# DVL_Interface.net
KiCad netlist of a schematic drawn in Altium Designer
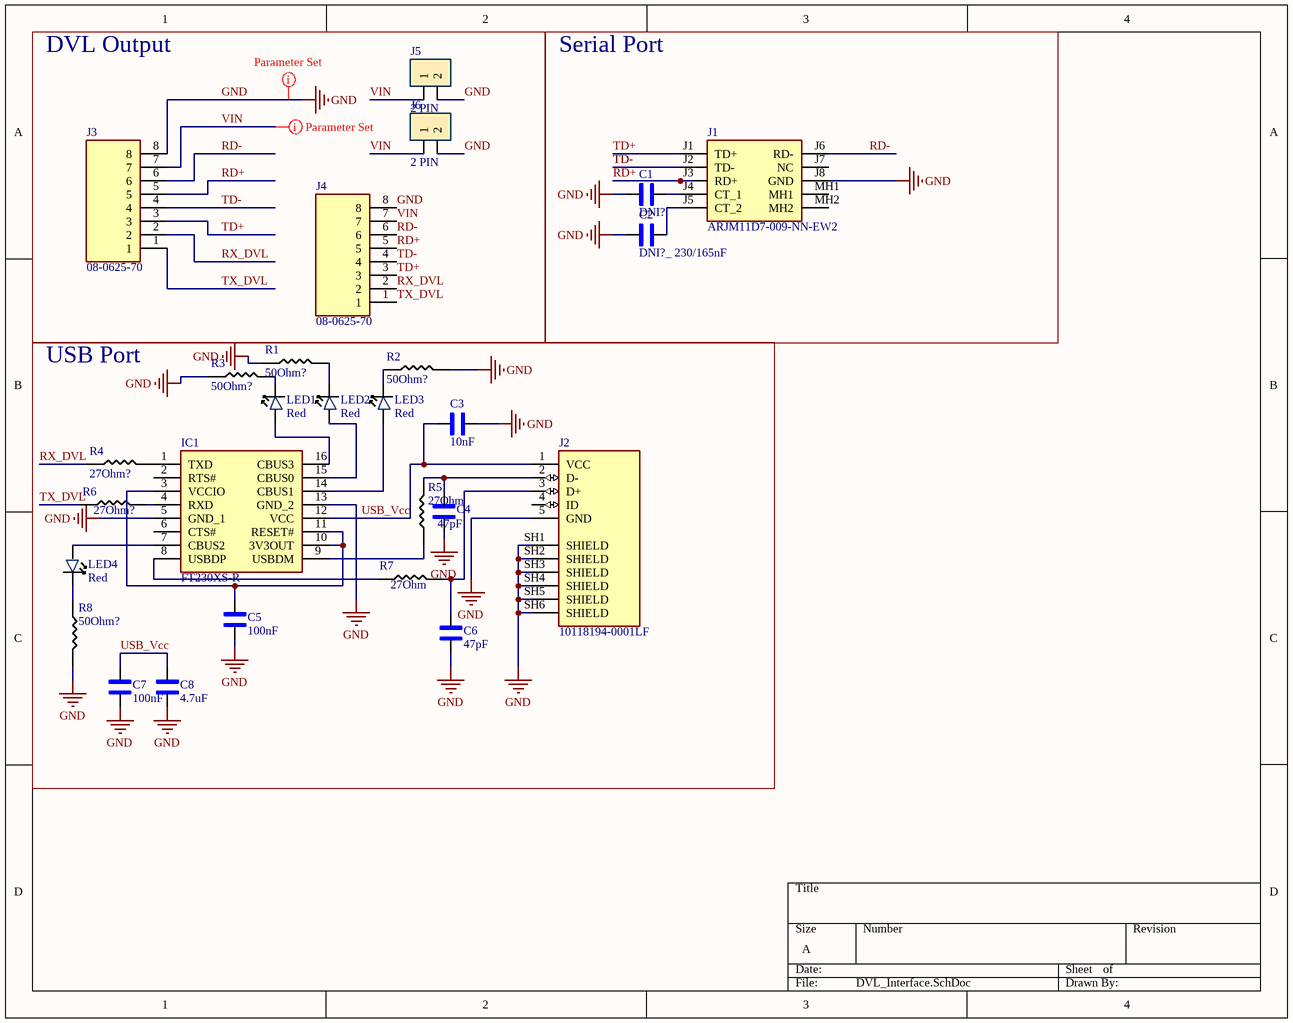
[diagram p0: DVL_Interface.SchDoc]

(export (version "E")
  (design (tool "Eeschema 10.0.6"))
  (components
    (comp (ref "C1")
      (value "DNI?")
      (footprint "1206_Passive_Capacitor")
      (description "10uF ±10% 50V X5R 1206 Multilayer Ceramic Capacitors MLCC - SMD/SMT RoHS")
      (fields (field (name "LCSC PART#") "C13585") (field (name "MFR PART #") "CL31A106KBHNNNE"))
      (libsource (lib "ECEN5730Lib_2023_05_DS") (part "C_10uF_1206"))
    )
    (comp (ref "C2")
      (value "DNI?_ 230/165nF")
      (footprint "1206_Passive_Capacitor")
      (description "10uF ±10% 50V X5R 1206 Multilayer Ceramic Capacitors MLCC - SMD/SMT RoHS")
      (fields (field (name "LCSC PART#") "C13585") (field (name "MFR PART #") "CL31A106KBHNNNE"))
      (libsource (lib "ECEN5730Lib_2023_05_DS") (part "C_10uF_1206"))
    )
    (comp (ref "C3")
      (value "10nF")
      (footprint "1206_Passive_Capacitor")
      (description "10uF ±10% 50V X5R 1206 Multilayer Ceramic Capacitors MLCC - SMD/SMT RoHS")
      (fields (field (name "LCSC PART#") "C13585") (field (name "MFR PART #") "CL31A106KBHNNNE"))
      (libsource (lib "ECEN5730Lib_2023_05_DS") (part "C_10uF_1206"))
    )
    (comp (ref "C4")
      (value "47pF")
      (footprint "1206_Passive_Capacitor")
      (description "47nF ±5% 50V C0G 1206 Multilayer Ceramic Capacitors MLCC - SMD/SMT RoHS")
      (fields (field (name "LCSC PART#") "C21812") (field (name "MFR PART #") "GRM31M5C1H473JA01L"))
      (libsource (lib "ECEN5730Lib_2023_05_DS") (part "C_47nF_1206"))
    )
    (comp (ref "C5")
      (value "100nF")
      (footprint "1206_Passive_Capacitor")
      (description "10uF ±10% 50V X5R 1206 Multilayer Ceramic Capacitors MLCC - SMD/SMT RoHS")
      (fields (field (name "LCSC PART#") "C13585") (field (name "MFR PART #") "CL31A106KBHNNNE"))
      (libsource (lib "ECEN5730Lib_2023_05_DS") (part "C_10uF_1206"))
    )
    (comp (ref "C6")
      (value "47pF")
      (footprint "1206_Passive_Capacitor")
      (description "47nF ±5% 50V C0G 1206 Multilayer Ceramic Capacitors MLCC - SMD/SMT RoHS")
      (fields (field (name "LCSC PART#") "C21812") (field (name "MFR PART #") "GRM31M5C1H473JA01L"))
      (libsource (lib "ECEN5730Lib_2023_05_DS") (part "C_47nF_1206"))
    )
    (comp (ref "C7")
      (value "100nF")
      (footprint "1206_Passive_Capacitor")
      (description "10uF ±10% 50V X5R 1206 Multilayer Ceramic Capacitors MLCC - SMD/SMT RoHS")
      (fields (field (name "LCSC PART#") "C13585") (field (name "MFR PART #") "CL31A106KBHNNNE"))
      (libsource (lib "ECEN5730Lib_2023_05_DS") (part "C_10uF_1206"))
    )
    (comp (ref "C8")
      (value "4.7uF")
      (footprint "1206_Passive_Capacitor")
      (description "10uF ±10% 50V X5R 1206 Multilayer Ceramic Capacitors MLCC - SMD/SMT RoHS")
      (fields (field (name "LCSC PART#") "C13585") (field (name "MFR PART #") "CL31A106KBHNNNE"))
      (libsource (lib "ECEN5730Lib_2023_05_DS") (part "C_10uF_1206"))
    )
    (comp (ref "IC1")
      (value "FT230XS-R")
      (footprint "SamacSys:SOP64P599X175-16N")
      (description "Integrated Circuit")
      (fields (field (name "MOUSER PART NUMBER") "895-FT230XS-R"))
      (libsource (lib "*") (part "FT230XS-R"))
    )
    (comp (ref "J1")
      (value "ARJM11D7-009-NN-EW2")
      (footprint "SamacSys:ARJM11D7009NNEW2")
      (description "Connector")
      (fields (field (name "MOUSER PART NUMBER") "815-RJM11D7009NNEW2"))
      (libsource (lib "*") (part "ARJM11D7-009-NN-EW2"))
    )
    (comp (ref "J2")
      (value "10118194-0001LF")
      (footprint "AMPHENOL_10118194-0001LF")
      (description "Micro USB, Input Output Connectors, B TYPE RECEPTACLE with flange")
      (fields (field (name "MF") "Amphenol ICC"))
      (libsource (lib "10118194-0001LF") (part "10118194-0001LF"))
    )
    (comp (ref "J3")
      (value "08-0625-70")
      (footprint "SamacSys:HDRV8W51P0X254_1X8_2032X254X816P")
      (description "Connector")
      (fields (field (name "MOUSER PART NUMBER") "535-08-0625-70"))
      (libsource (lib "*") (part "08-0625-70"))
    )
    (comp (ref "J4")
      (value "08-0625-70")
      (footprint "SamacSys:HDRV8W51P0X254_1X8_2032X254X816P")
      (description "Connector")
      (fields (field (name "MOUSER PART NUMBER") "535-08-0625-70"))
      (libsource (lib "*") (part "08-0625-70"))
    )
    (comp (ref "J5")
      (value "2 PIN")
      (footprint "2_PIN_100MIL")
      (description "2.54mm Straight 2 1 Header，Breakaway Through Hole,P=2.54mm Pin Header & Female Header ROHS")
      (fields (field (name "LCSC PART#") "C124375") (field (name "MFR PART #") "B-2100S02P-A110"))
      (libsource (lib "ECEN5730Lib_2023_05_DS") (part "JM_2_PIN_MALE"))
    )
    (comp (ref "J6")
      (value "2 PIN")
      (footprint "2_PIN_100MIL")
      (description "2.54mm Straight 2 1 Header，Breakaway Through Hole,P=2.54mm Pin Header & Female Header ROHS")
      (fields (field (name "LCSC PART#") "C124375") (field (name "MFR PART #") "B-2100S02P-A110"))
      (libsource (lib "ECEN5730Lib_2023_05_DS") (part "JM_2_PIN_MALE"))
    )
    (comp (ref "LED1")
      (value "Red")
      (footprint "LED_1206")
      (description "Red 621~631nm 1206 Light Emitting Diodes (LED) RoHS")
      (fields (field (name "MFR PART #") "15-21/R6C-FQ1R1B/2T") (field (name "LCSC PART#") "C93133"))
      (libsource (lib "ECEN5730Lib_2023_05_DS") (part "LED_RED_1206"))
    )
    (comp (ref "LED2")
      (value "Red")
      (footprint "LED_1206")
      (description "Red 621~631nm 1206 Light Emitting Diodes (LED) RoHS")
      (fields (field (name "MFR PART #") "15-21/R6C-FQ1R1B/2T") (field (name "LCSC PART#") "C93133"))
      (libsource (lib "ECEN5730Lib_2023_05_DS") (part "LED_RED_1206"))
    )
    (comp (ref "LED3")
      (value "Red")
      (footprint "LED_1206")
      (description "Red 621~631nm 1206 Light Emitting Diodes (LED) RoHS")
      (fields (field (name "MFR PART #") "15-21/R6C-FQ1R1B/2T") (field (name "LCSC PART#") "C93133"))
      (libsource (lib "ECEN5730Lib_2023_05_DS") (part "LED_RED_1206"))
    )
    (comp (ref "LED4")
      (value "Red")
      (footprint "LED_1206")
      (description "Red 621~631nm 1206 Light Emitting Diodes (LED) RoHS")
      (fields (field (name "MFR PART #") "15-21/R6C-FQ1R1B/2T") (field (name "LCSC PART#") "C93133"))
      (libsource (lib "ECEN5730Lib_2023_05_DS") (part "LED_RED_1206"))
    )
    (comp (ref "R1")
      (value "50Ohm?")
      (footprint "1206_Passive_Resitor")
      (description "10 kOhms ±5% 0.25W, 1/4W Chip Resistor 1206 (3216 Metric) Automotive AEC-Q200 Thick Film")
      (fields (field (name "MFR PART #") "RMCF1206FT10K0") (field (name "LCSC PART#") "C17902"))
      (libsource (lib "ECEN5730Lib_2023_05_DS") (part "R_10KOhm_1206"))
    )
    (comp (ref "R2")
      (value "50Ohm?")
      (footprint "1206_Passive_Resitor")
      (description "10 kOhms ±5% 0.25W, 1/4W Chip Resistor 1206 (3216 Metric) Automotive AEC-Q200 Thick Film")
      (fields (field (name "MFR PART #") "RMCF1206FT10K0") (field (name "LCSC PART#") "C17902"))
      (libsource (lib "ECEN5730Lib_2023_05_DS") (part "R_10KOhm_1206"))
    )
    (comp (ref "R3")
      (value "50Ohm?")
      (footprint "1206_Passive_Resitor")
      (description "10 kOhms ±5% 0.25W, 1/4W Chip Resistor 1206 (3216 Metric) Automotive AEC-Q200 Thick Film")
      (fields (field (name "MFR PART #") "RMCF1206FT10K0") (field (name "LCSC PART#") "C17902"))
      (libsource (lib "ECEN5730Lib_2023_05_DS") (part "R_10KOhm_1206"))
    )
    (comp (ref "R4")
      (value "27Ohm?")
      (footprint "1206_Passive_Resitor")
      (description "10 kOhms ±5% 0.25W, 1/4W Chip Resistor 1206 (3216 Metric) Automotive AEC-Q200 Thick Film")
      (fields (field (name "MFR PART #") "RMCF1206FT10K0") (field (name "LCSC PART#") "C17902"))
      (libsource (lib "ECEN5730Lib_2023_05_DS") (part "R_10KOhm_1206"))
    )
    (comp (ref "R5")
      (value "27Ohm")
      (footprint "1206_Passive_Resitor")
      (description "CHIP RESISTOR - SURFACE MOUNT 22OHMS ±1% 1/4W 1206 ROHS")
      (fields (field (name "MFR PART #") "1206W4F220JT5E") (field (name "LCSC PART#") "C17958"))
      (libsource (lib "ECEN5730Lib_2023_05_DS") (part "R_22Ohm_1206"))
    )
    (comp (ref "R6")
      (value "27Ohm?")
      (footprint "1206_Passive_Resitor")
      (description "10 kOhms ±5% 0.25W, 1/4W Chip Resistor 1206 (3216 Metric) Automotive AEC-Q200 Thick Film")
      (fields (field (name "MFR PART #") "RMCF1206FT10K0") (field (name "LCSC PART#") "C17902"))
      (libsource (lib "ECEN5730Lib_2023_05_DS") (part "R_10KOhm_1206"))
    )
    (comp (ref "R7")
      (value "27Ohm")
      (footprint "1206_Passive_Resitor")
      (description "CHIP RESISTOR - SURFACE MOUNT 22OHMS ±1% 1/4W 1206 ROHS")
      (fields (field (name "MFR PART #") "1206W4F220JT5E") (field (name "LCSC PART#") "C17958"))
      (libsource (lib "ECEN5730Lib_2023_05_DS") (part "R_22Ohm_1206"))
    )
    (comp (ref "R8")
      (value "50Ohm?")
      (footprint "1206_Passive_Resitor")
      (description "10 kOhms ±5% 0.25W, 1/4W Chip Resistor 1206 (3216 Metric) Automotive AEC-Q200 Thick Film")
      (fields (field (name "MFR PART #") "RMCF1206FT10K0") (field (name "LCSC PART#") "C17902"))
      (libsource (lib "ECEN5730Lib_2023_05_DS") (part "R_10KOhm_1206"))
    )
  )
  (nets
    (net (code "1") (name "/RD+") (class "Default")
      (node (ref "J1") (pin "J3") (pinfunction "RD+_J3") (pintype "passive"))
      (node (ref "J3") (pin "5") (pinfunction "5_5") (pintype "passive"))
      (node (ref "J4") (pin "5") (pinfunction "5_5") (pintype "passive"))
    )
    (net (code "2") (name "/RD-") (class "Default")
      (node (ref "J1") (pin "J6") (pinfunction "RD-_J6") (pintype "passive"))
      (node (ref "J3") (pin "6") (pinfunction "6_6") (pintype "passive"))
      (node (ref "J4") (pin "6") (pinfunction "6_6") (pintype "passive"))
    )
    (net (code "3") (name "/RX_DVL") (class "Default")
      (node (ref "J3") (pin "2") (pinfunction "2_2") (pintype "passive"))
      (node (ref "J4") (pin "2") (pinfunction "2_2") (pintype "passive"))
      (node (ref "R4") (pin "1") (pinfunction "1_1") (pintype "passive"))
    )
    (net (code "4") (name "/TD+") (class "Default")
      (node (ref "J1") (pin "J1") (pinfunction "TD+_J1") (pintype "passive"))
      (node (ref "J3") (pin "3") (pinfunction "3_3") (pintype "passive"))
      (node (ref "J4") (pin "3") (pinfunction "3_3") (pintype "passive"))
    )
    (net (code "5") (name "/TD-") (class "Default")
      (node (ref "J1") (pin "J2") (pinfunction "TD-_J2") (pintype "passive"))
      (node (ref "J3") (pin "4") (pinfunction "4_4") (pintype "passive"))
      (node (ref "J4") (pin "4") (pinfunction "4_4") (pintype "passive"))
    )
    (net (code "6") (name "/TX_DVL") (class "Default")
      (node (ref "J3") (pin "1") (pinfunction "1_1") (pintype "passive"))
      (node (ref "J4") (pin "1") (pinfunction "1_1") (pintype "passive"))
      (node (ref "R6") (pin "1") (pinfunction "1_1") (pintype "passive"))
    )
    (net (code "7") (name "/USB_Vcc") (class "Default")
      (node (ref "C3") (pin "2") (pinfunction "2_2") (pintype "passive"))
      (node (ref "C7") (pin "2") (pinfunction "2_2") (pintype "passive"))
      (node (ref "C8") (pin "2") (pinfunction "2_2") (pintype "passive"))
      (node (ref "IC1") (pin "12") (pinfunction "VCC_12") (pintype "passive"))
      (node (ref "J2") (pin "1") (pinfunction "VCC_1") (pintype "power_in"))
    )
    (net (code "8") (name "/VIN") (class "Default")
      (node (ref "J3") (pin "7") (pinfunction "7_7") (pintype "passive"))
      (node (ref "J4") (pin "7") (pinfunction "7_7") (pintype "passive"))
      (node (ref "J5") (pin "1") (pinfunction "1_1") (pintype "passive"))
      (node (ref "J6") (pin "1") (pinfunction "1_1") (pintype "passive"))
    )
    (net (code "9") (name "GND") (class "Default")
      (node (ref "C1") (pin "2") (pinfunction "2_2") (pintype "passive"))
      (node (ref "C2") (pin "2") (pinfunction "2_2") (pintype "passive"))
      (node (ref "C3") (pin "1") (pinfunction "1_1") (pintype "passive"))
      (node (ref "C4") (pin "1") (pinfunction "1_1") (pintype "passive"))
      (node (ref "C5") (pin "1") (pinfunction "1_1") (pintype "passive"))
      (node (ref "C6") (pin "1") (pinfunction "1_1") (pintype "passive"))
      (node (ref "C7") (pin "1") (pinfunction "1_1") (pintype "passive"))
      (node (ref "C8") (pin "1") (pinfunction "1_1") (pintype "passive"))
      (node (ref "IC1") (pin "13") (pinfunction "GND_2_13") (pintype "passive"))
      (node (ref "IC1") (pin "5") (pinfunction "GND_1_5") (pintype "passive"))
      (node (ref "J1") (pin "J8") (pinfunction "GND_J8") (pintype "passive"))
      (node (ref "J2") (pin "5") (pinfunction "GND_5") (pintype "power_in"))
      (node (ref "J2") (pin "SH1") (pinfunction "SHIELD_SH1") (pintype "passive"))
      (node (ref "J2") (pin "SH2") (pinfunction "SHIELD_SH2") (pintype "passive"))
      (node (ref "J2") (pin "SH3") (pinfunction "SHIELD_SH3") (pintype "passive"))
      (node (ref "J2") (pin "SH4") (pinfunction "SHIELD_SH4") (pintype "passive"))
      (node (ref "J2") (pin "SH5") (pinfunction "SHIELD_SH5") (pintype "passive"))
      (node (ref "J2") (pin "SH6") (pinfunction "SHIELD_SH6") (pintype "passive"))
      (node (ref "J3") (pin "8") (pinfunction "8_8") (pintype "passive"))
      (node (ref "J4") (pin "8") (pinfunction "8_8") (pintype "passive"))
      (node (ref "J5") (pin "2") (pinfunction "2_2") (pintype "passive"))
      (node (ref "J6") (pin "2") (pinfunction "2_2") (pintype "passive"))
      (node (ref "R1") (pin "1") (pinfunction "1_1") (pintype "passive"))
      (node (ref "R2") (pin "2") (pinfunction "2_2") (pintype "passive"))
      (node (ref "R3") (pin "1") (pinfunction "1_1") (pintype "passive"))
      (node (ref "R8") (pin "2") (pinfunction "2_2") (pintype "passive"))
    )
    (net (code "10") (name "Net-(IC1-3V3OUT)") (class "Default")
      (node (ref "C5") (pin "2") (pinfunction "2_2") (pintype "passive"))
      (node (ref "IC1") (pin "10") (pinfunction "3V3OUT_10") (pintype "passive"))
      (node (ref "IC1") (pin "11") (pinfunction "RESET#_11") (pintype "passive"))
      (node (ref "IC1") (pin "3") (pinfunction "VCCIO_3") (pintype "passive"))
    )
    (net (code "11") (name "Net-(IC1-CBUS0)") (class "Default")
      (node (ref "IC1") (pin "15") (pinfunction "CBUS0_15") (pintype "passive"))
      (node (ref "LED2") (pin "1") (pinfunction "1_1") (pintype "passive"))
    )
    (net (code "12") (name "Net-(IC1-CBUS1)") (class "Default")
      (node (ref "IC1") (pin "14") (pinfunction "CBUS1_14") (pintype "passive"))
      (node (ref "LED3") (pin "1") (pinfunction "1_1") (pintype "passive"))
    )
    (net (code "13") (name "Net-(IC1-CBUS2)") (class "Default")
      (node (ref "IC1") (pin "7") (pinfunction "CBUS2_7") (pintype "passive"))
      (node (ref "LED4") (pin "1") (pinfunction "1_1") (pintype "passive"))
    )
    (net (code "14") (name "Net-(IC1-CBUS3)") (class "Default")
      (node (ref "IC1") (pin "16") (pinfunction "CBUS3_16") (pintype "passive"))
      (node (ref "LED1") (pin "1") (pinfunction "1_1") (pintype "passive"))
    )
    (net (code "15") (name "Net-(IC1-RXD)") (class "Default")
      (node (ref "IC1") (pin "4") (pinfunction "RXD_4") (pintype "passive"))
      (node (ref "R6") (pin "2") (pinfunction "2_2") (pintype "passive"))
    )
    (net (code "16") (name "Net-(IC1-TXD)") (class "Default")
      (node (ref "IC1") (pin "1") (pinfunction "TXD_1") (pintype "passive"))
      (node (ref "R4") (pin "2") (pinfunction "2_2") (pintype "passive"))
    )
    (net (code "17") (name "Net-(IC1-USBDM)") (class "Default")
      (node (ref "IC1") (pin "9") (pinfunction "USBDM_9") (pintype "passive"))
      (node (ref "R5") (pin "1") (pinfunction "1_1") (pintype "passive"))
    )
    (net (code "18") (name "Net-(IC1-USBDP)") (class "Default")
      (node (ref "IC1") (pin "8") (pinfunction "USBDP_8") (pintype "passive"))
      (node (ref "R7") (pin "1") (pinfunction "1_1") (pintype "passive"))
    )
    (net (code "19") (name "Net-(J1-CT_1)") (class "Default")
      (node (ref "C1") (pin "1") (pinfunction "1_1") (pintype "passive"))
      (node (ref "J1") (pin "J4") (pinfunction "CT_1_J4") (pintype "passive"))
    )
    (net (code "20") (name "Net-(J1-CT_2)") (class "Default")
      (node (ref "C2") (pin "1") (pinfunction "1_1") (pintype "passive"))
      (node (ref "J1") (pin "J5") (pinfunction "CT_2_J5") (pintype "passive"))
    )
    (net (code "21") (name "Net-(J2-D+)") (class "Default")
      (node (ref "C6") (pin "2") (pinfunction "2_2") (pintype "passive"))
      (node (ref "J2") (pin "3") (pinfunction "D+_3") (pintype "bidirectional"))
      (node (ref "R7") (pin "2") (pinfunction "2_2") (pintype "passive"))
    )
    (net (code "22") (name "Net-(J2-D-)") (class "Default")
      (node (ref "C4") (pin "2") (pinfunction "2_2") (pintype "passive"))
      (node (ref "J2") (pin "2") (pinfunction "D-_2") (pintype "bidirectional"))
      (node (ref "R5") (pin "2") (pinfunction "2_2") (pintype "passive"))
    )
    (net (code "23") (name "Net-(LED1-Pad2)") (class "Default")
      (node (ref "LED1") (pin "2") (pinfunction "2_2") (pintype "passive"))
      (node (ref "R3") (pin "2") (pinfunction "2_2") (pintype "passive"))
    )
    (net (code "24") (name "Net-(LED2-Pad2)") (class "Default")
      (node (ref "LED2") (pin "2") (pinfunction "2_2") (pintype "passive"))
      (node (ref "R1") (pin "2") (pinfunction "2_2") (pintype "passive"))
    )
    (net (code "25") (name "Net-(LED3-Pad2)") (class "Default")
      (node (ref "LED3") (pin "2") (pinfunction "2_2") (pintype "passive"))
      (node (ref "R2") (pin "1") (pinfunction "1_1") (pintype "passive"))
    )
    (net (code "26") (name "Net-(LED4-Pad2)") (class "Default")
      (node (ref "LED4") (pin "2") (pinfunction "2_2") (pintype "passive"))
      (node (ref "R8") (pin "1") (pinfunction "1_1") (pintype "passive"))
    )
    (net (code "27") (name "unconnected-(IC1-CTS#-Pad6)") (class "Default")
      (node (ref "IC1") (pin "6") (pinfunction "CTS#_6") (pintype "passive"))
    )
    (net (code "28") (name "unconnected-(IC1-RTS#-Pad2)") (class "Default")
      (node (ref "IC1") (pin "2") (pinfunction "RTS#_2") (pintype "passive"))
    )
    (net (code "29") (name "unconnected-(J1-NC-PadJ7)") (class "Default")
      (node (ref "J1") (pin "J7") (pinfunction "NC_J7") (pintype "passive"))
    )
    (net (code "30") (name "unconnected-(J1-PadMH1)") (class "Default")
      (node (ref "J1") (pin "MH1") (pinfunction "MH1_MH1") (pintype "passive"))
    )
    (net (code "31") (name "unconnected-(J1-PadMH2)") (class "Default")
      (node (ref "J1") (pin "MH2") (pinfunction "MH2_MH2") (pintype "passive"))
    )
    (net (code "32") (name "unconnected-(J2-ID-Pad4)") (class "Default")
      (node (ref "J2") (pin "4") (pinfunction "ID_4") (pintype "bidirectional"))
    )
  )
)
